# AutoDownload.net
KiCad netlist of a schematic drawn in Altium Designer
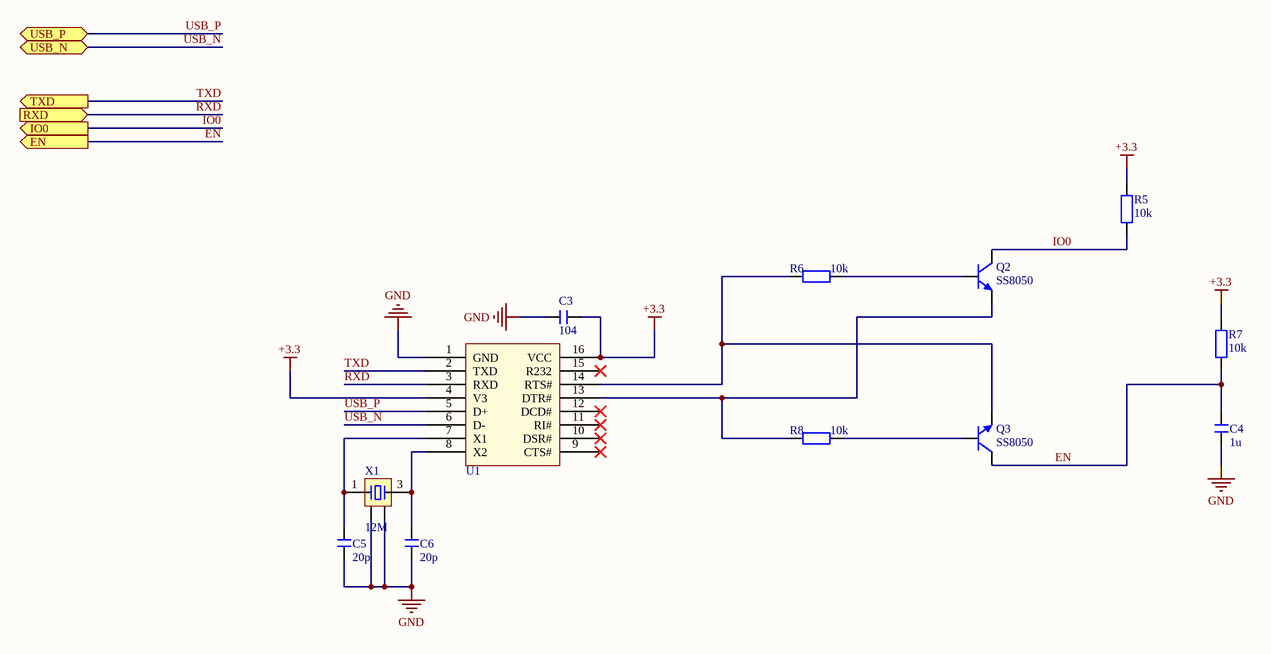
[diagram p0: AutoDownload.SchDoc]

(export (version "E")
  (design (tool "Eeschema 10.0.6"))
  (components
    (comp (ref "C3")
      (value "104")
      (footprint "C 0603-L")
      (description "贴片电容")
      (libsource (lib "0.1 - 电阻-电容-电感") (part "C"))
    )
    (comp (ref "C4")
      (value "1u")
      (footprint "C 0603-L")
      (description "贴片电容")
      (libsource (lib "0.1 - 电阻-电容-电感") (part "C"))
    )
    (comp (ref "C5")
      (value "20p")
      (footprint "C 0603-L")
      (description "贴片电容")
      (libsource (lib "0.1 - 电阻-电容-电感") (part "C"))
    )
    (comp (ref "C6")
      (value "20p")
      (footprint "C 0603-L")
      (description "贴片电容")
      (libsource (lib "0.1 - 电阻-电容-电感") (part "C"))
    )
    (comp (ref "Q2")
      (value "SS8050")
      (footprint "SOT23-3N")
      (description "高频放大-NPN型")
      (libsource (lib "0.4 - 三极管-场效应管-可控硅") (part "8050-SMD"))
    )
    (comp (ref "Q3")
      (value "SS8050")
      (footprint "SOT23-3N")
      (description "高频放大-NPN型")
      (libsource (lib "0.4 - 三极管-场效应管-可控硅") (part "8050-SMD"))
    )
    (comp (ref "R5")
      (value "10k")
      (footprint "R 0603_L")
      (description "贴片电阻")
      (libsource (lib "0.1 - 电阻-电容-电感") (part "R"))
    )
    (comp (ref "R6")
      (value "10k")
      (footprint "R 0603_L")
      (description "贴片电阻")
      (libsource (lib "0.1 - 电阻-电容-电感") (part "R"))
    )
    (comp (ref "R7")
      (value "10k")
      (footprint "R 0603_L")
      (description "贴片电阻")
      (libsource (lib "0.1 - 电阻-电容-电感") (part "R"))
    )
    (comp (ref "R8")
      (value "10k")
      (footprint "R 0603_L")
      (description "贴片电阻")
      (libsource (lib "0.1 - 电阻-电容-电感") (part "R"))
    )
    (comp (ref "U1")
      (value "CH340G")
      (footprint "sop16_L")
      (libsource (lib "1.9 - CH340系列编程器芯片") (part "CH340G"))
    )
    (comp (ref "X1")
      (value "12M")
      (footprint "OSC 3225-4P")
      (description "4脚无源晶振")
      (fields (field (name "版权归属") "封装库来自淘宝卖家 ID：黄晶宝石"))
      (libsource (lib "0.5 - 保险丝-晶振-光耦") (part "XTAL-4P"))
    )
  )
  (nets
    (net (code "1") (name "+3.3") (class "Default")
      (node (ref "C3") (pin "2") (pinfunction "2_2") (pintype "passive"))
      (node (ref "R5") (pin "2") (pinfunction "2_2") (pintype "passive"))
      (node (ref "R7") (pin "2") (pinfunction "2_2") (pintype "passive"))
      (node (ref "U1") (pin "16") (pinfunction "VCC_16") (pintype "passive"))
      (node (ref "U1") (pin "4") (pinfunction "V3_4") (pintype "passive"))
    )
    (net (code "2") (name "/EN") (class "Default")
      (node (ref "C4") (pin "2") (pinfunction "2_2") (pintype "passive"))
      (node (ref "Q3") (pin "3") (pinfunction "C_3") (pintype "passive"))
      (node (ref "R7") (pin "1") (pinfunction "1_1") (pintype "passive"))
    )
    (net (code "3") (name "/IO0") (class "Default")
      (node (ref "Q2") (pin "3") (pinfunction "C_3") (pintype "passive"))
      (node (ref "R5") (pin "1") (pinfunction "1_1") (pintype "passive"))
    )
    (net (code "4") (name "/RXD") (class "Default")
      (node (ref "U1") (pin "3") (pinfunction "RXD_3") (pintype "passive"))
    )
    (net (code "5") (name "/TXD") (class "Default")
      (node (ref "U1") (pin "2") (pinfunction "TXD_2") (pintype "passive"))
    )
    (net (code "6") (name "/USB_N") (class "Default")
      (node (ref "U1") (pin "6") (pinfunction "D-_6") (pintype "passive"))
    )
    (net (code "7") (name "/USB_P") (class "Default")
      (node (ref "U1") (pin "5") (pinfunction "D+_5") (pintype "passive"))
    )
    (net (code "8") (name "GND") (class "Default")
      (node (ref "C3") (pin "1") (pinfunction "1_1") (pintype "passive"))
      (node (ref "C4") (pin "1") (pinfunction "1_1") (pintype "passive"))
      (node (ref "C5") (pin "1") (pinfunction "1_1") (pintype "passive"))
      (node (ref "C6") (pin "1") (pinfunction "1_1") (pintype "passive"))
      (node (ref "U1") (pin "1") (pinfunction "GND_1") (pintype "passive"))
      (node (ref "X1") (pin "2") (pinfunction "2_2") (pintype "passive"))
      (node (ref "X1") (pin "4") (pinfunction "4_4") (pintype "passive"))
    )
    (net (code "9") (name "Net-(Q2-B)") (class "Default")
      (node (ref "Q2") (pin "1") (pinfunction "B_1") (pintype "passive"))
      (node (ref "R6") (pin "2") (pinfunction "2_2") (pintype "passive"))
    )
    (net (code "10") (name "Net-(Q2-E)") (class "Default")
      (node (ref "Q2") (pin "2") (pinfunction "E_2") (pintype "passive"))
      (node (ref "R8") (pin "1") (pinfunction "1_1") (pintype "passive"))
      (node (ref "U1") (pin "13") (pinfunction "DTR#_13") (pintype "passive"))
    )
    (net (code "11") (name "Net-(Q3-B)") (class "Default")
      (node (ref "Q3") (pin "1") (pinfunction "B_1") (pintype "passive"))
      (node (ref "R8") (pin "2") (pinfunction "2_2") (pintype "passive"))
    )
    (net (code "12") (name "Net-(Q3-E)") (class "Default")
      (node (ref "Q3") (pin "2") (pinfunction "E_2") (pintype "passive"))
      (node (ref "R6") (pin "1") (pinfunction "1_1") (pintype "passive"))
      (node (ref "U1") (pin "14") (pinfunction "RTS#_14") (pintype "passive"))
    )
    (net (code "13") (name "Net-(U1-X1)") (class "Default")
      (node (ref "C5") (pin "2") (pinfunction "2_2") (pintype "passive"))
      (node (ref "U1") (pin "7") (pinfunction "X1_7") (pintype "passive"))
      (node (ref "X1") (pin "1") (pinfunction "1_1") (pintype "passive"))
    )
    (net (code "14") (name "Net-(U1-X2)") (class "Default")
      (node (ref "C6") (pin "2") (pinfunction "2_2") (pintype "passive"))
      (node (ref "U1") (pin "8") (pinfunction "X2_8") (pintype "passive"))
      (node (ref "X1") (pin "3") (pinfunction "3_3") (pintype "passive"))
    )
    (net (code "15") (name "unconnected-(U1-CTS#-Pad9)") (class "Default")
      (node (ref "U1") (pin "9") (pinfunction "CTS#_9") (pintype "passive+no_connect"))
    )
    (net (code "16") (name "unconnected-(U1-DCD#-Pad12)") (class "Default")
      (node (ref "U1") (pin "12") (pinfunction "DCD#_12") (pintype "passive+no_connect"))
    )
    (net (code "17") (name "unconnected-(U1-DSR#-Pad10)") (class "Default")
      (node (ref "U1") (pin "10") (pinfunction "DSR#_10") (pintype "passive+no_connect"))
    )
    (net (code "18") (name "unconnected-(U1-R232-Pad15)") (class "Default")
      (node (ref "U1") (pin "15") (pinfunction "R232_15") (pintype "passive+no_connect"))
    )
    (net (code "19") (name "unconnected-(U1-RI#-Pad11)") (class "Default")
      (node (ref "U1") (pin "11") (pinfunction "RI#_11") (pintype "passive+no_connect"))
    )
  )
)
